# SCH_Sensor-Wind_EasyEDA.net
KiCad netlist of a schematic drawn in EasyEDA
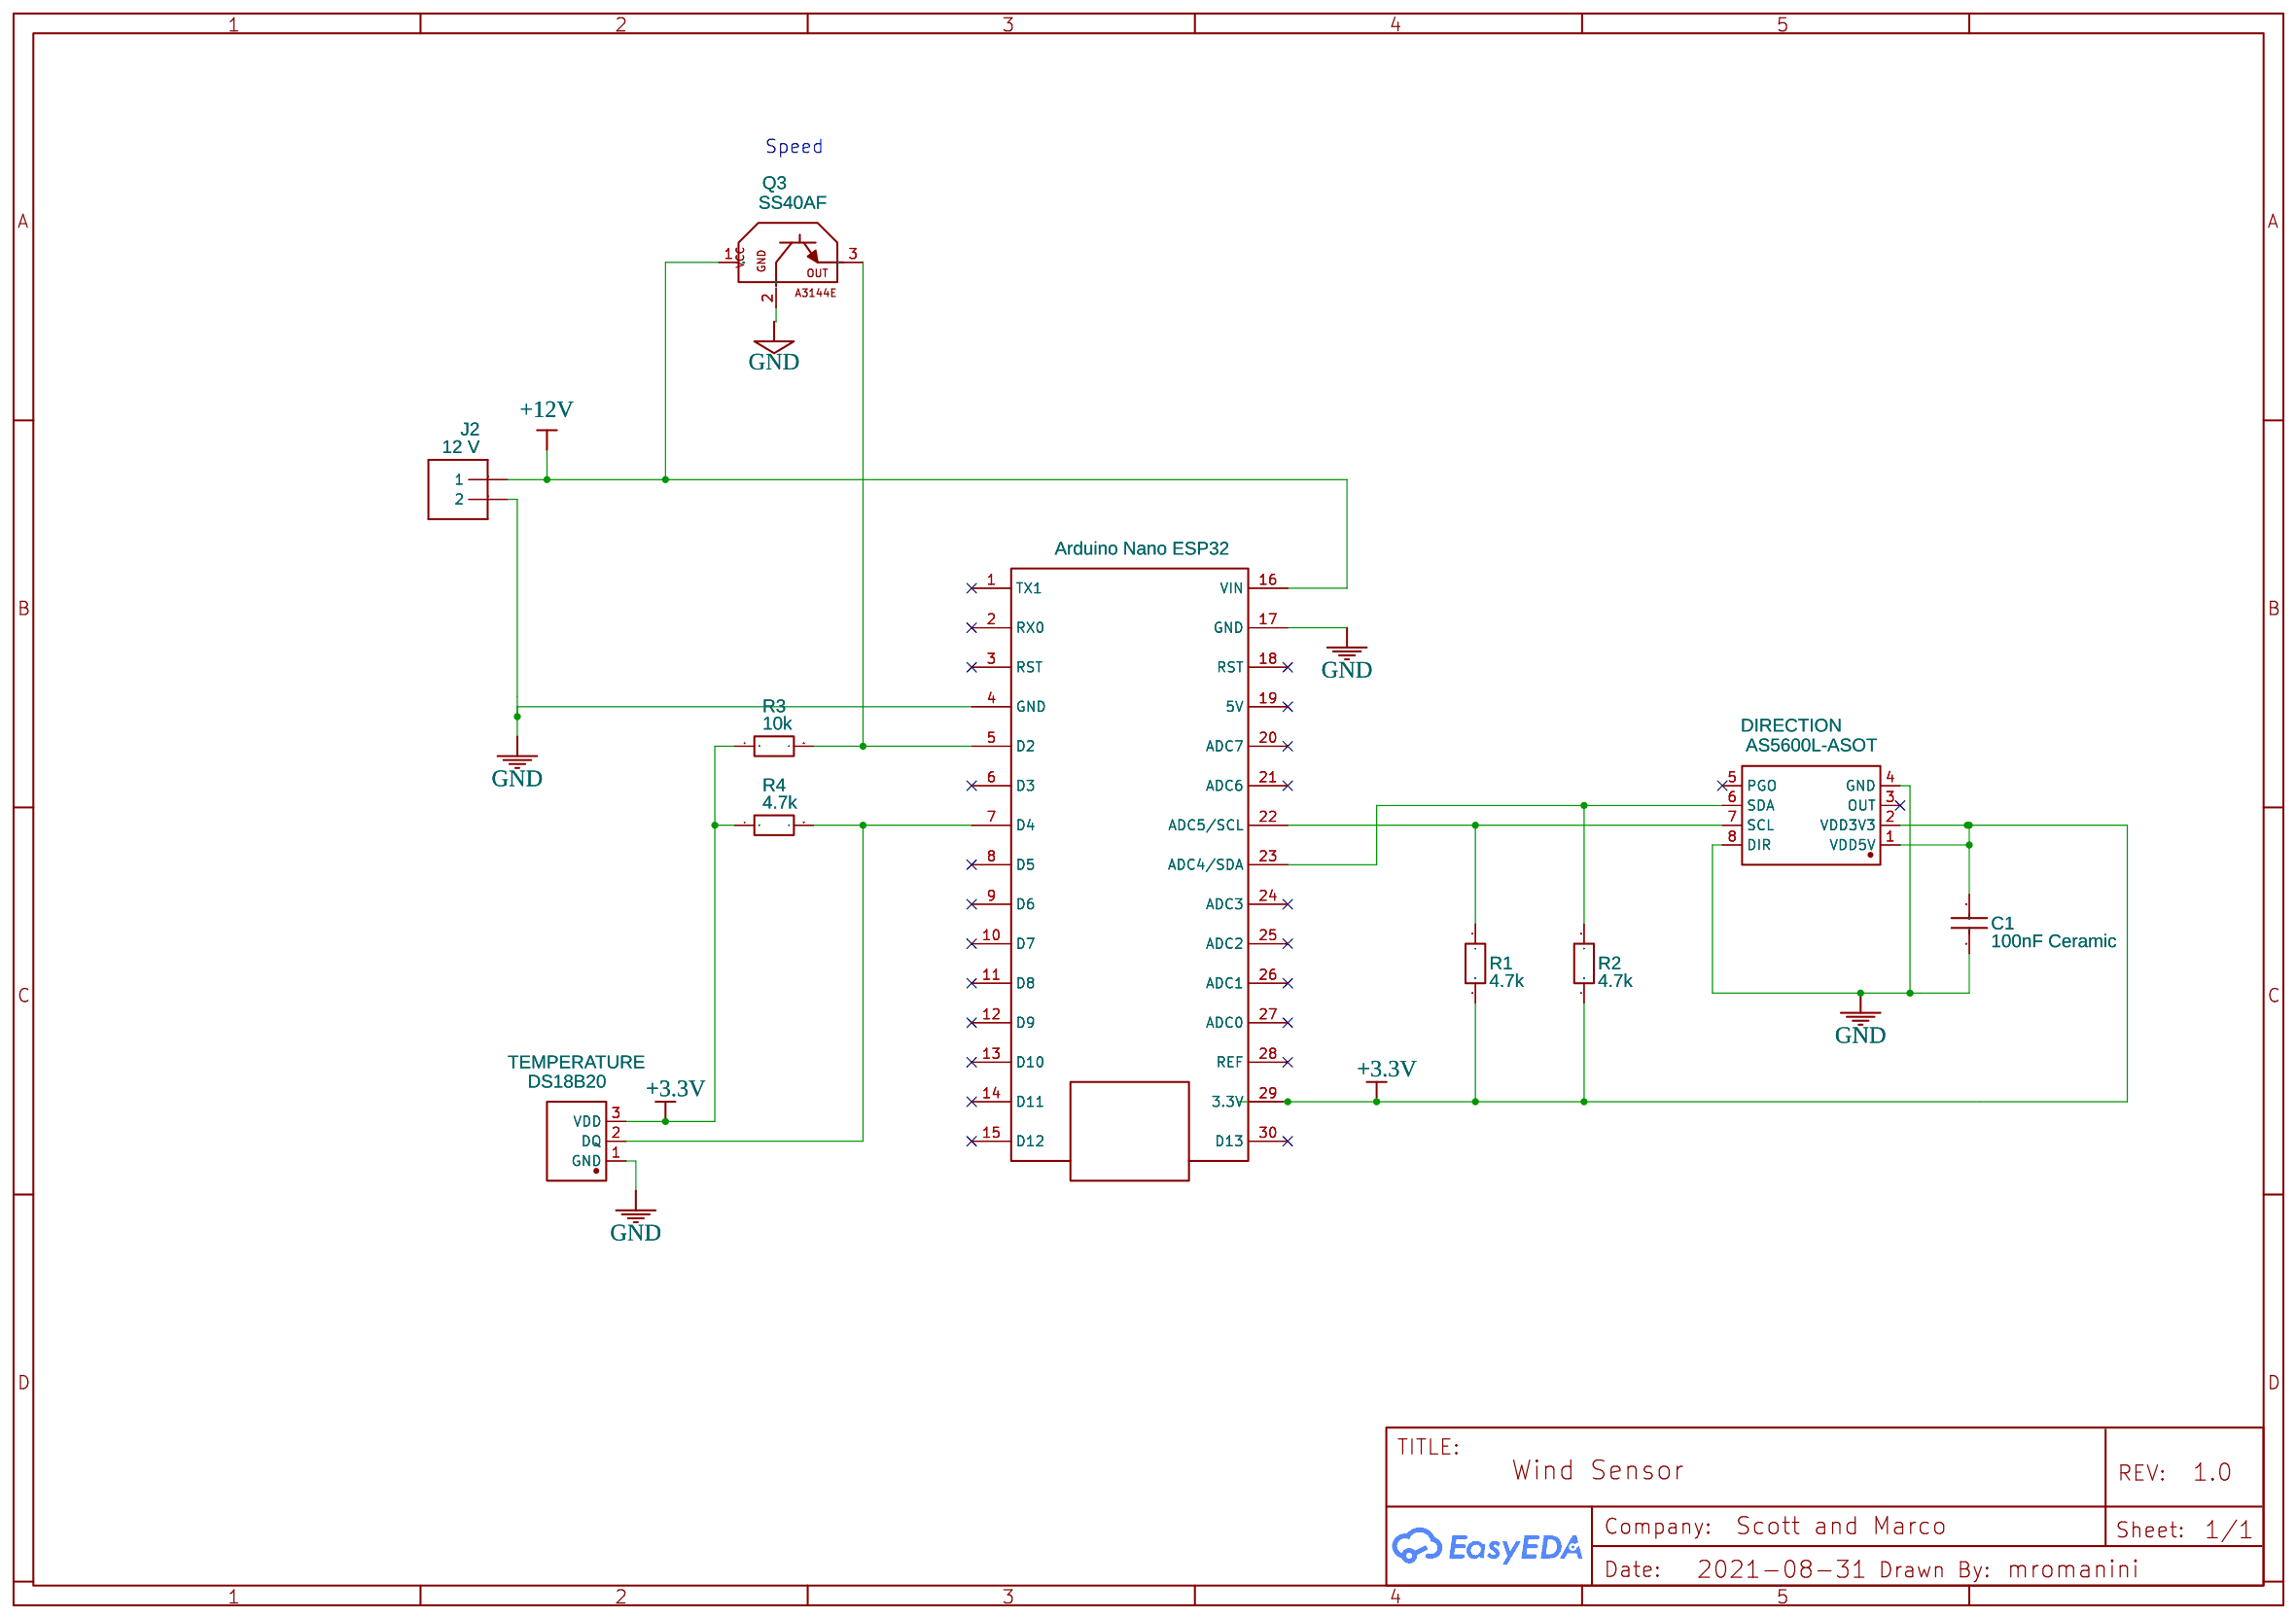
[diagram p0: schematic sheet]

(export (version "E")
  (design (tool "Eeschema 10.0.6"))
  (components
    (comp (ref "C1")
      (value "100nF Ceramic")
      (fields (field (name "Manufacturer Part") "Capacitor_Ceramic"))
      (libsource (lib "") (part "Capacitor_Ceramic"))
    )
    (comp (ref "DIRECTION")
      (value "AS5600L-ASOT")
      (fields (field (name "Manufacturer") "美国AMS"))
      (libsource (lib "") (part "AS5600L-ASOM"))
    )
    (comp (ref "J2") (value "12 V") (libsource (lib "") (part "TERMBLOCK_1X2-3.5MM")))
    (comp (ref "Q3")
      (value "SS40AF")
      (fields (field (name "Manufacturer") "Honeywell"))
      (libsource (lib "") (part "A3144E_HALLSENSOR_COPY"))
    )
    (comp (ref "R1") (value "4.7k") (libsource (lib "") (part "1w resistor_1")))
    (comp (ref "R2") (value "4.7k") (libsource (lib "") (part "1w resistor_1")))
    (comp (ref "R3") (value "10k") (libsource (lib "") (part "1w resistor")))
    (comp (ref "R4") (value "4.7k") (libsource (lib "") (part "1w resistor")))
    (comp (ref "TEMPERATURE")
      (value "DS18B20")
      (fields (field (name "Manufacturer") "Youtai Semiconductor Co., Ltd."))
      (libsource (lib "") (part "DS18B20"))
    )
    (comp (ref "U1") (value "Arduino Nano ESP32") (libsource (lib "") (part "ARDUINO_NANO_R3")))
  )
  (nets
    (net (code "1") (name "+3.3V") (class "Default")
      (node (ref "C1") (pin "1") (pinfunction "1_1") (pintype "unspecified"))
      (node (ref "DIRECTION") (pin "1") (pinfunction "VDD5V_1") (pintype "unspecified"))
      (node (ref "DIRECTION") (pin "2") (pinfunction "VDD3V3_2") (pintype "unspecified"))
      (node (ref "R1") (pin "1") (pinfunction "2_1") (pintype "unspecified"))
      (node (ref "R2") (pin "1") (pinfunction "2_1") (pintype "unspecified"))
      (node (ref "R3") (pin "1") (pinfunction "2_1") (pintype "unspecified"))
      (node (ref "R4") (pin "1") (pinfunction "2_1") (pintype "unspecified"))
      (node (ref "TEMPERATURE") (pin "3") (pinfunction "VDD_3") (pintype "unspecified"))
      (node (ref "U1") (pin "29") (pinfunction "3.3V_29") (pintype "unspecified"))
    )
    (net (code "2") (name "+12V") (class "Default")
      (node (ref "J2") (pin "1") (pinfunction "1_1") (pintype "bidirectional"))
      (node (ref "Q3") (pin "1") (pinfunction "Supply_1") (pintype "unspecified"))
      (node (ref "U1") (pin "16") (pinfunction "VIN_16") (pintype "unspecified"))
    )
    (net (code "3") (name "GND") (class "Default")
      (node (ref "C1") (pin "2") (pinfunction "2_2") (pintype "unspecified"))
      (node (ref "DIRECTION") (pin "4") (pinfunction "GND_4") (pintype "unspecified"))
      (node (ref "DIRECTION") (pin "8") (pinfunction "DIR_8") (pintype "unspecified"))
      (node (ref "J2") (pin "2") (pinfunction "2_2") (pintype "bidirectional"))
      (node (ref "Q3") (pin "2") (pinfunction "Ground_2") (pintype "unspecified"))
      (node (ref "TEMPERATURE") (pin "1") (pinfunction "GND_1") (pintype "unspecified"))
      (node (ref "U1") (pin "17") (pinfunction "GND_17") (pintype "unspecified"))
      (node (ref "U1") (pin "4") (pinfunction "GND_4") (pintype "unspecified"))
    )
    (net (code "4") (name "Net-(DIRECTION-SCL)") (class "Default")
      (node (ref "DIRECTION") (pin "7") (pinfunction "SCL_7") (pintype "unspecified"))
      (node (ref "R1") (pin "2") (pinfunction "1_2") (pintype "unspecified"))
      (node (ref "U1") (pin "22") (pinfunction "ADC5/SCL_22") (pintype "unspecified"))
    )
    (net (code "5") (name "Net-(DIRECTION-SDA)") (class "Default")
      (node (ref "DIRECTION") (pin "6") (pinfunction "SDA_6") (pintype "unspecified"))
      (node (ref "R2") (pin "2") (pinfunction "1_2") (pintype "unspecified"))
      (node (ref "U1") (pin "23") (pinfunction "ADC4/SDA_23") (pintype "unspecified"))
    )
    (net (code "6") (name "Net-(Q3-Output)") (class "Default")
      (node (ref "Q3") (pin "3") (pinfunction "Output_3") (pintype "unspecified"))
      (node (ref "R3") (pin "2") (pinfunction "1_2") (pintype "unspecified"))
      (node (ref "U1") (pin "5") (pinfunction "D2_5") (pintype "unspecified"))
    )
    (net (code "7") (name "Net-(R4-1)") (class "Default")
      (node (ref "R4") (pin "2") (pinfunction "1_2") (pintype "unspecified"))
      (node (ref "TEMPERATURE") (pin "2") (pinfunction "DQ_2") (pintype "unspecified"))
      (node (ref "U1") (pin "7") (pinfunction "D4_7") (pintype "unspecified"))
    )
    (net (code "8") (name "unconnected-(DIRECTION-OUT-Pad3)") (class "Default")
      (node (ref "DIRECTION") (pin "3") (pinfunction "OUT_3") (pintype "unspecified+no_connect"))
    )
    (net (code "9") (name "unconnected-(DIRECTION-PGO-Pad5)") (class "Default")
      (node (ref "DIRECTION") (pin "5") (pinfunction "PGO_5") (pintype "unspecified+no_connect"))
    )
    (net (code "10") (name "unconnected-(U1-5V-Pad19)") (class "Default")
      (node (ref "U1") (pin "19") (pinfunction "5V_19") (pintype "unspecified+no_connect"))
    )
    (net (code "11") (name "unconnected-(U1-ADC0-Pad27)") (class "Default")
      (node (ref "U1") (pin "27") (pinfunction "ADC0_27") (pintype "unspecified+no_connect"))
    )
    (net (code "12") (name "unconnected-(U1-ADC1-Pad26)") (class "Default")
      (node (ref "U1") (pin "26") (pinfunction "ADC1_26") (pintype "unspecified+no_connect"))
    )
    (net (code "13") (name "unconnected-(U1-ADC2-Pad25)") (class "Default")
      (node (ref "U1") (pin "25") (pinfunction "ADC2_25") (pintype "unspecified+no_connect"))
    )
    (net (code "14") (name "unconnected-(U1-ADC3-Pad24)") (class "Default")
      (node (ref "U1") (pin "24") (pinfunction "ADC3_24") (pintype "unspecified+no_connect"))
    )
    (net (code "15") (name "unconnected-(U1-ADC6-Pad21)") (class "Default")
      (node (ref "U1") (pin "21") (pinfunction "ADC6_21") (pintype "unspecified+no_connect"))
    )
    (net (code "16") (name "unconnected-(U1-ADC7-Pad20)") (class "Default")
      (node (ref "U1") (pin "20") (pinfunction "ADC7_20") (pintype "unspecified+no_connect"))
    )
    (net (code "17") (name "unconnected-(U1-D3-Pad6)") (class "Default")
      (node (ref "U1") (pin "6") (pinfunction "D3_6") (pintype "unspecified+no_connect"))
    )
    (net (code "18") (name "unconnected-(U1-D5-Pad8)") (class "Default")
      (node (ref "U1") (pin "8") (pinfunction "D5_8") (pintype "unspecified+no_connect"))
    )
    (net (code "19") (name "unconnected-(U1-D6-Pad9)") (class "Default")
      (node (ref "U1") (pin "9") (pinfunction "D6_9") (pintype "unspecified+no_connect"))
    )
    (net (code "20") (name "unconnected-(U1-D7-Pad10)") (class "Default")
      (node (ref "U1") (pin "10") (pinfunction "D7_10") (pintype "unspecified+no_connect"))
    )
    (net (code "21") (name "unconnected-(U1-D8-Pad11)") (class "Default")
      (node (ref "U1") (pin "11") (pinfunction "D8_11") (pintype "unspecified+no_connect"))
    )
    (net (code "22") (name "unconnected-(U1-D9-Pad12)") (class "Default")
      (node (ref "U1") (pin "12") (pinfunction "D9_12") (pintype "unspecified+no_connect"))
    )
    (net (code "23") (name "unconnected-(U1-D10-Pad13)") (class "Default")
      (node (ref "U1") (pin "13") (pinfunction "D10_13") (pintype "unspecified+no_connect"))
    )
    (net (code "24") (name "unconnected-(U1-D11-Pad14)") (class "Default")
      (node (ref "U1") (pin "14") (pinfunction "D11_14") (pintype "unspecified+no_connect"))
    )
    (net (code "25") (name "unconnected-(U1-D12-Pad15)") (class "Default")
      (node (ref "U1") (pin "15") (pinfunction "D12_15") (pintype "unspecified+no_connect"))
    )
    (net (code "26") (name "unconnected-(U1-D13-Pad30)") (class "Default")
      (node (ref "U1") (pin "30") (pinfunction "D13_30") (pintype "unspecified+no_connect"))
    )
    (net (code "27") (name "unconnected-(U1-REF-Pad28)") (class "Default")
      (node (ref "U1") (pin "28") (pinfunction "REF_28") (pintype "unspecified+no_connect"))
    )
    (net (code "28") (name "unconnected-(U1-RST-Pad3)") (class "Default")
      (node (ref "U1") (pin "3") (pinfunction "RST_3") (pintype "unspecified+no_connect"))
    )
    (net (code "29") (name "unconnected-(U1-RST-Pad18)") (class "Default")
      (node (ref "U1") (pin "18") (pinfunction "RST_18") (pintype "unspecified+no_connect"))
    )
    (net (code "30") (name "unconnected-(U1-RX0-Pad2)") (class "Default")
      (node (ref "U1") (pin "2") (pinfunction "RX0_2") (pintype "unspecified+no_connect"))
    )
    (net (code "31") (name "unconnected-(U1-TX1-Pad1)") (class "Default")
      (node (ref "U1") (pin "1") (pinfunction "TX1_1") (pintype "unspecified+no_connect"))
    )
  )
)
